# DIOT_signal_routing.net
KiCad netlist of a schematic drawn in Altium Designer
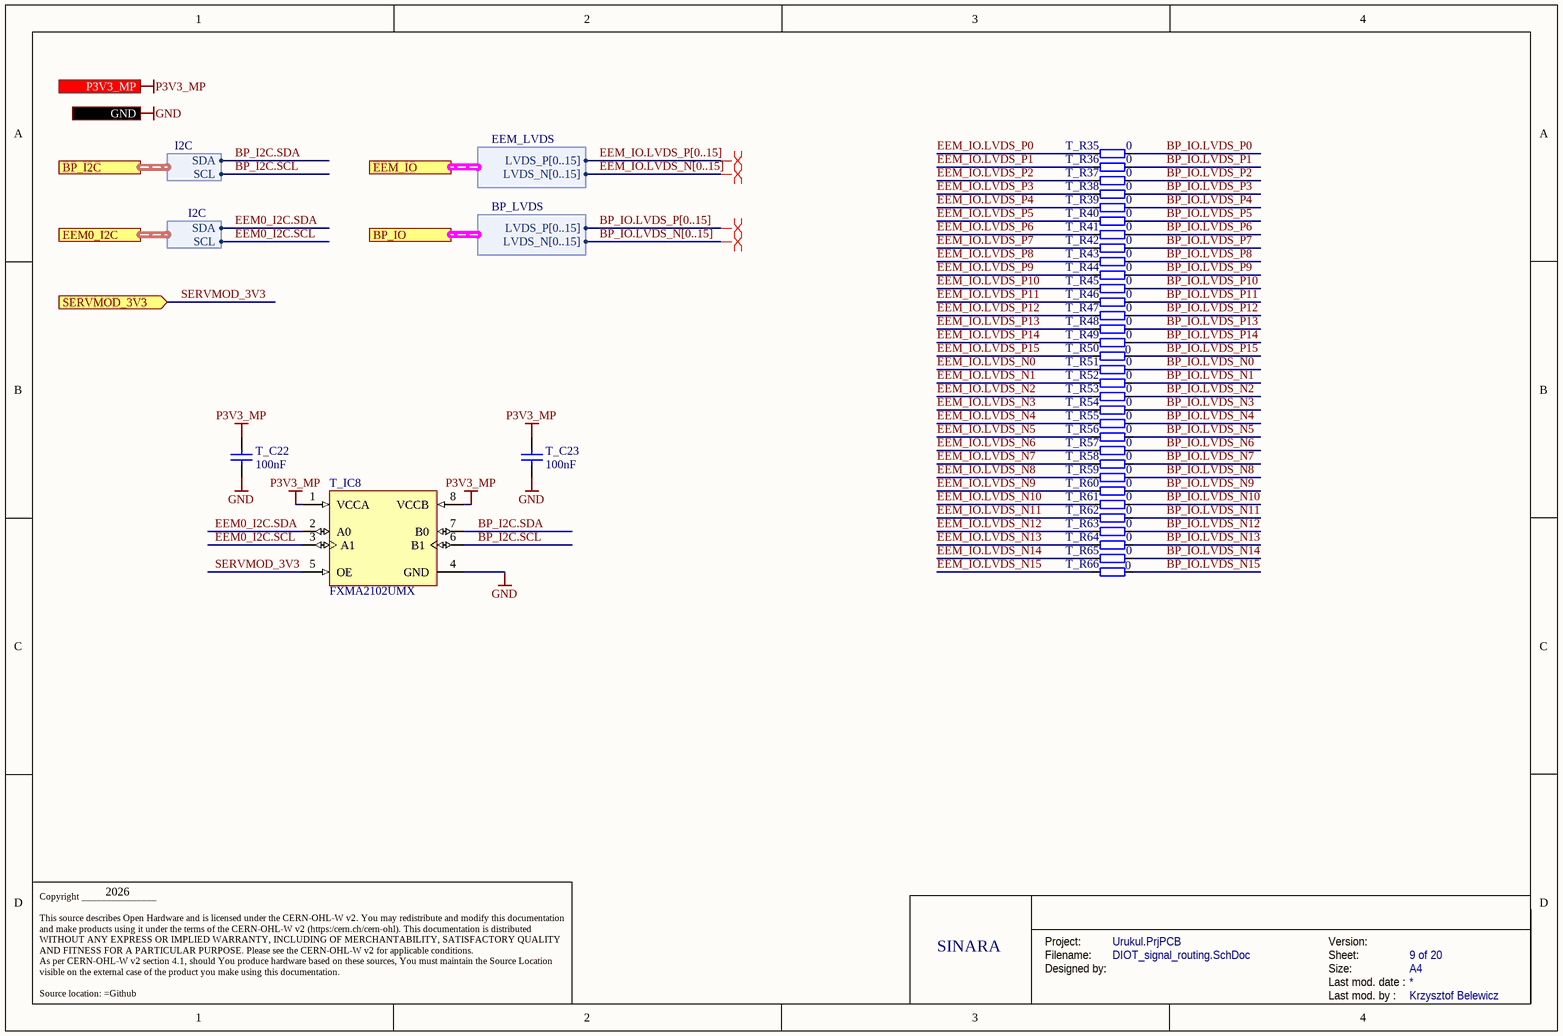
[diagram p0: DIOT_signal_routing.SchDoc]

(export (version "E")
  (design (tool "Eeschema 10.0.6"))
  (components
    (comp (ref "T_C22")
      (value "100nF")
      (footprint "CAPC1005X55N")
      (description "Non-polarised capacitor")
      (fields
        (field (name "PART NUMBER") "CC0402_100NF_16V_10%_X5R")
        (field (name "VOLTAGE") "16V")
        (field (name "AUTHOR") "CERN DEM JLC")
      )
      (libsource (lib "Capacitors") (part "Capacitor - non polarized"))
    )
    (comp (ref "T_C23")
      (value "100nF")
      (footprint "CAPC1005X55N")
      (description "Non-polarised capacitor")
      (fields
        (field (name "PART NUMBER") "CC0402_100NF_16V_10%_X5R")
        (field (name "VOLTAGE") "16V")
        (field (name "AUTHOR") "CERN DEM JLC")
      )
      (libsource (lib "Capacitors") (part "Capacitor - non polarized"))
    )
    (comp (ref "T_IC8")
      (value "FXMA2102UMX")
      (footprint "FXMA2102UMX")
      (description "Dual Supply 2-Bit Voltage Translator/Buffer/Repeater Isolator for I2C Applications")
      (fields (field (name "MANUFACTURER") "Onsemi"))
      (libsource (lib "TechnoSystem Workspace") (part "FXMA2102UMX"))
    )
    (comp (ref "T_R35")
      (value "0")
      (footprint "RESC1005X40N")
      (description "Resistor")
      (fields
        (field (name "PART NUMBER") "R0402_0R_JUMPER")
        (field (name "MANUFACTURER") "GENERIC")
        (field (name "AUTHOR") "CERN DEM JLC")
      )
      (libsource (lib "Resistors") (part "Resistor"))
    )
    (comp (ref "T_R36")
      (value "0")
      (footprint "RESC1005X40N")
      (description "Resistor")
      (fields
        (field (name "PART NUMBER") "R0402_0R_JUMPER")
        (field (name "MANUFACTURER") "GENERIC")
        (field (name "AUTHOR") "CERN DEM JLC")
      )
      (libsource (lib "Resistors") (part "Resistor"))
    )
    (comp (ref "T_R37")
      (value "0")
      (footprint "RESC1005X40N")
      (description "Resistor")
      (fields
        (field (name "PART NUMBER") "R0402_0R_JUMPER")
        (field (name "MANUFACTURER") "GENERIC")
        (field (name "AUTHOR") "CERN DEM JLC")
      )
      (libsource (lib "Resistors") (part "Resistor"))
    )
    (comp (ref "T_R38")
      (value "0")
      (footprint "RESC1005X40N")
      (description "Resistor")
      (fields
        (field (name "PART NUMBER") "R0402_0R_JUMPER")
        (field (name "MANUFACTURER") "GENERIC")
        (field (name "AUTHOR") "CERN DEM JLC")
      )
      (libsource (lib "Resistors") (part "Resistor"))
    )
    (comp (ref "T_R39")
      (value "0")
      (footprint "RESC1005X40N")
      (description "Resistor")
      (fields
        (field (name "PART NUMBER") "R0402_0R_JUMPER")
        (field (name "MANUFACTURER") "GENERIC")
        (field (name "AUTHOR") "CERN DEM JLC")
      )
      (libsource (lib "Resistors") (part "Resistor"))
    )
    (comp (ref "T_R40")
      (value "0")
      (footprint "RESC1005X40N")
      (description "Resistor")
      (fields
        (field (name "PART NUMBER") "R0402_0R_JUMPER")
        (field (name "MANUFACTURER") "GENERIC")
        (field (name "AUTHOR") "CERN DEM JLC")
      )
      (libsource (lib "Resistors") (part "Resistor"))
    )
    (comp (ref "T_R41")
      (value "0")
      (footprint "RESC1005X40N")
      (description "Resistor")
      (fields
        (field (name "PART NUMBER") "R0402_0R_JUMPER")
        (field (name "MANUFACTURER") "GENERIC")
        (field (name "AUTHOR") "CERN DEM JLC")
      )
      (libsource (lib "Resistors") (part "Resistor"))
    )
    (comp (ref "T_R42")
      (value "0")
      (footprint "RESC1005X40N")
      (description "Resistor")
      (fields
        (field (name "PART NUMBER") "R0402_0R_JUMPER")
        (field (name "MANUFACTURER") "GENERIC")
        (field (name "AUTHOR") "CERN DEM JLC")
      )
      (libsource (lib "Resistors") (part "Resistor"))
    )
    (comp (ref "T_R43")
      (value "0")
      (footprint "RESC1005X40N")
      (description "Resistor")
      (fields
        (field (name "PART NUMBER") "R0402_0R_JUMPER")
        (field (name "MANUFACTURER") "GENERIC")
        (field (name "AUTHOR") "CERN DEM JLC")
      )
      (libsource (lib "Resistors") (part "Resistor"))
    )
    (comp (ref "T_R44")
      (value "0")
      (footprint "RESC1005X40N")
      (description "Resistor")
      (fields
        (field (name "PART NUMBER") "R0402_0R_JUMPER")
        (field (name "MANUFACTURER") "GENERIC")
        (field (name "AUTHOR") "CERN DEM JLC")
      )
      (libsource (lib "Resistors") (part "Resistor"))
    )
    (comp (ref "T_R45")
      (value "0")
      (footprint "RESC1005X40N")
      (description "Resistor")
      (fields
        (field (name "PART NUMBER") "R0402_0R_JUMPER")
        (field (name "MANUFACTURER") "GENERIC")
        (field (name "AUTHOR") "CERN DEM JLC")
      )
      (libsource (lib "Resistors") (part "Resistor"))
    )
    (comp (ref "T_R46")
      (value "0")
      (footprint "RESC1005X40N")
      (description "Resistor")
      (fields
        (field (name "PART NUMBER") "R0402_0R_JUMPER")
        (field (name "MANUFACTURER") "GENERIC")
        (field (name "AUTHOR") "CERN DEM JLC")
      )
      (libsource (lib "Resistors") (part "Resistor"))
    )
    (comp (ref "T_R47")
      (value "0")
      (footprint "RESC1005X40N")
      (description "Resistor")
      (fields
        (field (name "PART NUMBER") "R0402_0R_JUMPER")
        (field (name "MANUFACTURER") "GENERIC")
        (field (name "AUTHOR") "CERN DEM JLC")
      )
      (libsource (lib "Resistors") (part "Resistor"))
    )
    (comp (ref "T_R48")
      (value "0")
      (footprint "RESC1005X40N")
      (description "Resistor")
      (fields
        (field (name "PART NUMBER") "R0402_0R_JUMPER")
        (field (name "MANUFACTURER") "GENERIC")
        (field (name "AUTHOR") "CERN DEM JLC")
      )
      (libsource (lib "Resistors") (part "Resistor"))
    )
    (comp (ref "T_R49")
      (value "0")
      (footprint "RESC1005X40N")
      (description "Resistor")
      (fields
        (field (name "PART NUMBER") "R0402_0R_JUMPER")
        (field (name "MANUFACTURER") "GENERIC")
        (field (name "AUTHOR") "CERN DEM JLC")
      )
      (libsource (lib "Resistors") (part "Resistor"))
    )
    (comp (ref "T_R50")
      (value "0")
      (footprint "RESC1005X40N")
      (description "Resistor")
      (fields
        (field (name "PART NUMBER") "R0402_0R_JUMPER")
        (field (name "MANUFACTURER") "GENERIC")
        (field (name "AUTHOR") "CERN DEM JLC")
      )
      (libsource (lib "Resistors") (part "Resistor"))
    )
    (comp (ref "T_R51")
      (value "0")
      (footprint "RESC1005X40N")
      (description "Resistor")
      (fields
        (field (name "PART NUMBER") "R0402_0R_JUMPER")
        (field (name "MANUFACTURER") "GENERIC")
        (field (name "AUTHOR") "CERN DEM JLC")
      )
      (libsource (lib "Resistors") (part "Resistor"))
    )
    (comp (ref "T_R52")
      (value "0")
      (footprint "RESC1005X40N")
      (description "Resistor")
      (fields
        (field (name "PART NUMBER") "R0402_0R_JUMPER")
        (field (name "MANUFACTURER") "GENERIC")
        (field (name "AUTHOR") "CERN DEM JLC")
      )
      (libsource (lib "Resistors") (part "Resistor"))
    )
    (comp (ref "T_R53")
      (value "0")
      (footprint "RESC1005X40N")
      (description "Resistor")
      (fields
        (field (name "PART NUMBER") "R0402_0R_JUMPER")
        (field (name "MANUFACTURER") "GENERIC")
        (field (name "AUTHOR") "CERN DEM JLC")
      )
      (libsource (lib "Resistors") (part "Resistor"))
    )
    (comp (ref "T_R54")
      (value "0")
      (footprint "RESC1005X40N")
      (description "Resistor")
      (fields
        (field (name "PART NUMBER") "R0402_0R_JUMPER")
        (field (name "MANUFACTURER") "GENERIC")
        (field (name "AUTHOR") "CERN DEM JLC")
      )
      (libsource (lib "Resistors") (part "Resistor"))
    )
    (comp (ref "T_R55")
      (value "0")
      (footprint "RESC1005X40N")
      (description "Resistor")
      (fields
        (field (name "PART NUMBER") "R0402_0R_JUMPER")
        (field (name "MANUFACTURER") "GENERIC")
        (field (name "AUTHOR") "CERN DEM JLC")
      )
      (libsource (lib "Resistors") (part "Resistor"))
    )
    (comp (ref "T_R56")
      (value "0")
      (footprint "RESC1005X40N")
      (description "Resistor")
      (fields
        (field (name "PART NUMBER") "R0402_0R_JUMPER")
        (field (name "MANUFACTURER") "GENERIC")
        (field (name "AUTHOR") "CERN DEM JLC")
      )
      (libsource (lib "Resistors") (part "Resistor"))
    )
    (comp (ref "T_R57")
      (value "0")
      (footprint "RESC1005X40N")
      (description "Resistor")
      (fields
        (field (name "PART NUMBER") "R0402_0R_JUMPER")
        (field (name "MANUFACTURER") "GENERIC")
        (field (name "AUTHOR") "CERN DEM JLC")
      )
      (libsource (lib "Resistors") (part "Resistor"))
    )
    (comp (ref "T_R58")
      (value "0")
      (footprint "RESC1005X40N")
      (description "Resistor")
      (fields
        (field (name "PART NUMBER") "R0402_0R_JUMPER")
        (field (name "MANUFACTURER") "GENERIC")
        (field (name "AUTHOR") "CERN DEM JLC")
      )
      (libsource (lib "Resistors") (part "Resistor"))
    )
    (comp (ref "T_R59")
      (value "0")
      (footprint "RESC1005X40N")
      (description "Resistor")
      (fields
        (field (name "PART NUMBER") "R0402_0R_JUMPER")
        (field (name "MANUFACTURER") "GENERIC")
        (field (name "AUTHOR") "CERN DEM JLC")
      )
      (libsource (lib "Resistors") (part "Resistor"))
    )
    (comp (ref "T_R60")
      (value "0")
      (footprint "RESC1005X40N")
      (description "Resistor")
      (fields
        (field (name "PART NUMBER") "R0402_0R_JUMPER")
        (field (name "MANUFACTURER") "GENERIC")
        (field (name "AUTHOR") "CERN DEM JLC")
      )
      (libsource (lib "Resistors") (part "Resistor"))
    )
    (comp (ref "T_R61")
      (value "0")
      (footprint "RESC1005X40N")
      (description "Resistor")
      (fields
        (field (name "PART NUMBER") "R0402_0R_JUMPER")
        (field (name "MANUFACTURER") "GENERIC")
        (field (name "AUTHOR") "CERN DEM JLC")
      )
      (libsource (lib "Resistors") (part "Resistor"))
    )
    (comp (ref "T_R62")
      (value "0")
      (footprint "RESC1005X40N")
      (description "Resistor")
      (fields
        (field (name "PART NUMBER") "R0402_0R_JUMPER")
        (field (name "MANUFACTURER") "GENERIC")
        (field (name "AUTHOR") "CERN DEM JLC")
      )
      (libsource (lib "Resistors") (part "Resistor"))
    )
    (comp (ref "T_R63")
      (value "0")
      (footprint "RESC1005X40N")
      (description "Resistor")
      (fields
        (field (name "PART NUMBER") "R0402_0R_JUMPER")
        (field (name "MANUFACTURER") "GENERIC")
        (field (name "AUTHOR") "CERN DEM JLC")
      )
      (libsource (lib "Resistors") (part "Resistor"))
    )
    (comp (ref "T_R64")
      (value "0")
      (footprint "RESC1005X40N")
      (description "Resistor")
      (fields
        (field (name "PART NUMBER") "R0402_0R_JUMPER")
        (field (name "MANUFACTURER") "GENERIC")
        (field (name "AUTHOR") "CERN DEM JLC")
      )
      (libsource (lib "Resistors") (part "Resistor"))
    )
    (comp (ref "T_R65")
      (value "0")
      (footprint "RESC1005X40N")
      (description "Resistor")
      (fields
        (field (name "PART NUMBER") "R0402_0R_JUMPER")
        (field (name "MANUFACTURER") "GENERIC")
        (field (name "AUTHOR") "CERN DEM JLC")
      )
      (libsource (lib "Resistors") (part "Resistor"))
    )
    (comp (ref "T_R66")
      (value "0")
      (footprint "RESC1005X40N")
      (description "Resistor")
      (fields
        (field (name "PART NUMBER") "R0402_0R_JUMPER")
        (field (name "MANUFACTURER") "GENERIC")
        (field (name "AUTHOR") "CERN DEM JLC")
      )
      (libsource (lib "Resistors") (part "Resistor"))
    )
  )
  (nets
    (net (code "4") (name "/BP_I2C.SCL") (class "Default")
      (node (ref "T_IC8") (pin "6") (pinfunction "B1_6") (pintype "bidirectional"))
    )
    (net (code "5") (name "/BP_I2C.SDA") (class "Default")
      (node (ref "T_IC8") (pin "7") (pinfunction "B0_7") (pintype "bidirectional"))
    )
    (net (code "6") (name "/BP_IO.LVDS_N0") (class "Default")
      (node (ref "T_R51") (pin "1") (pinfunction "1_1") (pintype "passive"))
    )
    (net (code "7") (name "/BP_IO.LVDS_N1") (class "Default")
      (node (ref "T_R52") (pin "1") (pinfunction "1_1") (pintype "passive"))
    )
    (net (code "8") (name "/BP_IO.LVDS_N2") (class "Default")
      (node (ref "T_R53") (pin "1") (pinfunction "1_1") (pintype "passive"))
    )
    (net (code "9") (name "/BP_IO.LVDS_N3") (class "Default")
      (node (ref "T_R54") (pin "1") (pinfunction "1_1") (pintype "passive"))
    )
    (net (code "10") (name "/BP_IO.LVDS_N4") (class "Default")
      (node (ref "T_R55") (pin "1") (pinfunction "1_1") (pintype "passive"))
    )
    (net (code "11") (name "/BP_IO.LVDS_N5") (class "Default")
      (node (ref "T_R56") (pin "1") (pinfunction "1_1") (pintype "passive"))
    )
    (net (code "12") (name "/BP_IO.LVDS_N6") (class "Default")
      (node (ref "T_R57") (pin "1") (pinfunction "1_1") (pintype "passive"))
    )
    (net (code "13") (name "/BP_IO.LVDS_N7") (class "Default")
      (node (ref "T_R58") (pin "1") (pinfunction "1_1") (pintype "passive"))
    )
    (net (code "14") (name "/BP_IO.LVDS_N8") (class "Default")
      (node (ref "T_R59") (pin "1") (pinfunction "1_1") (pintype "passive"))
    )
    (net (code "15") (name "/BP_IO.LVDS_N9") (class "Default")
      (node (ref "T_R60") (pin "1") (pinfunction "1_1") (pintype "passive"))
    )
    (net (code "16") (name "/BP_IO.LVDS_N10") (class "Default")
      (node (ref "T_R61") (pin "1") (pinfunction "1_1") (pintype "passive"))
    )
    (net (code "17") (name "/BP_IO.LVDS_N11") (class "Default")
      (node (ref "T_R62") (pin "1") (pinfunction "1_1") (pintype "passive"))
    )
    (net (code "18") (name "/BP_IO.LVDS_N12") (class "Default")
      (node (ref "T_R63") (pin "1") (pinfunction "1_1") (pintype "passive"))
    )
    (net (code "19") (name "/BP_IO.LVDS_N13") (class "Default")
      (node (ref "T_R64") (pin "1") (pinfunction "1_1") (pintype "passive"))
    )
    (net (code "20") (name "/BP_IO.LVDS_N14") (class "Default")
      (node (ref "T_R65") (pin "1") (pinfunction "1_1") (pintype "passive"))
    )
    (net (code "21") (name "/BP_IO.LVDS_N15") (class "Default")
      (node (ref "T_R66") (pin "2") (pinfunction "2_2") (pintype "passive"))
    )
    (net (code "22") (name "/BP_IO.LVDS_P0") (class "Default")
      (node (ref "T_R35") (pin "1") (pinfunction "1_1") (pintype "passive"))
    )
    (net (code "23") (name "/BP_IO.LVDS_P1") (class "Default")
      (node (ref "T_R36") (pin "1") (pinfunction "1_1") (pintype "passive"))
    )
    (net (code "24") (name "/BP_IO.LVDS_P2") (class "Default")
      (node (ref "T_R37") (pin "1") (pinfunction "1_1") (pintype "passive"))
    )
    (net (code "25") (name "/BP_IO.LVDS_P3") (class "Default")
      (node (ref "T_R38") (pin "1") (pinfunction "1_1") (pintype "passive"))
    )
    (net (code "26") (name "/BP_IO.LVDS_P4") (class "Default")
      (node (ref "T_R39") (pin "1") (pinfunction "1_1") (pintype "passive"))
    )
    (net (code "27") (name "/BP_IO.LVDS_P5") (class "Default")
      (node (ref "T_R40") (pin "1") (pinfunction "1_1") (pintype "passive"))
    )
    (net (code "28") (name "/BP_IO.LVDS_P6") (class "Default")
      (node (ref "T_R41") (pin "1") (pinfunction "1_1") (pintype "passive"))
    )
    (net (code "29") (name "/BP_IO.LVDS_P7") (class "Default")
      (node (ref "T_R42") (pin "1") (pinfunction "1_1") (pintype "passive"))
    )
    (net (code "30") (name "/BP_IO.LVDS_P8") (class "Default")
      (node (ref "T_R43") (pin "1") (pinfunction "1_1") (pintype "passive"))
    )
    (net (code "31") (name "/BP_IO.LVDS_P9") (class "Default")
      (node (ref "T_R44") (pin "1") (pinfunction "1_1") (pintype "passive"))
    )
    (net (code "32") (name "/BP_IO.LVDS_P10") (class "Default")
      (node (ref "T_R45") (pin "1") (pinfunction "1_1") (pintype "passive"))
    )
    (net (code "33") (name "/BP_IO.LVDS_P11") (class "Default")
      (node (ref "T_R46") (pin "1") (pinfunction "1_1") (pintype "passive"))
    )
    (net (code "34") (name "/BP_IO.LVDS_P12") (class "Default")
      (node (ref "T_R47") (pin "1") (pinfunction "1_1") (pintype "passive"))
    )
    (net (code "35") (name "/BP_IO.LVDS_P13") (class "Default")
      (node (ref "T_R48") (pin "1") (pinfunction "1_1") (pintype "passive"))
    )
    (net (code "36") (name "/BP_IO.LVDS_P14") (class "Default")
      (node (ref "T_R49") (pin "1") (pinfunction "1_1") (pintype "passive"))
    )
    (net (code "37") (name "/BP_IO.LVDS_P15") (class "Default")
      (node (ref "T_R50") (pin "2") (pinfunction "2_2") (pintype "passive"))
    )
    (net (code "40") (name "/EEM0_I2C.SCL") (class "Default")
      (node (ref "T_IC8") (pin "3") (pinfunction "A1_3") (pintype "bidirectional"))
    )
    (net (code "41") (name "/EEM0_I2C.SDA") (class "Default")
      (node (ref "T_IC8") (pin "2") (pinfunction "A0_2") (pintype "bidirectional"))
    )
    (net (code "42") (name "/EEM_IO.LVDS_N0") (class "Default")
      (node (ref "T_R51") (pin "2") (pinfunction "2_2") (pintype "passive"))
    )
    (net (code "43") (name "/EEM_IO.LVDS_N1") (class "Default")
      (node (ref "T_R52") (pin "2") (pinfunction "2_2") (pintype "passive"))
    )
    (net (code "44") (name "/EEM_IO.LVDS_N2") (class "Default")
      (node (ref "T_R53") (pin "2") (pinfunction "2_2") (pintype "passive"))
    )
    (net (code "45") (name "/EEM_IO.LVDS_N3") (class "Default")
      (node (ref "T_R54") (pin "2") (pinfunction "2_2") (pintype "passive"))
    )
    (net (code "46") (name "/EEM_IO.LVDS_N4") (class "Default")
      (node (ref "T_R55") (pin "2") (pinfunction "2_2") (pintype "passive"))
    )
    (net (code "47") (name "/EEM_IO.LVDS_N5") (class "Default")
      (node (ref "T_R56") (pin "2") (pinfunction "2_2") (pintype "passive"))
    )
    (net (code "48") (name "/EEM_IO.LVDS_N6") (class "Default")
      (node (ref "T_R57") (pin "2") (pinfunction "2_2") (pintype "passive"))
    )
    (net (code "49") (name "/EEM_IO.LVDS_N7") (class "Default")
      (node (ref "T_R58") (pin "2") (pinfunction "2_2") (pintype "passive"))
    )
    (net (code "50") (name "/EEM_IO.LVDS_N8") (class "Default")
      (node (ref "T_R59") (pin "2") (pinfunction "2_2") (pintype "passive"))
    )
    (net (code "51") (name "/EEM_IO.LVDS_N9") (class "Default")
      (node (ref "T_R60") (pin "2") (pinfunction "2_2") (pintype "passive"))
    )
    (net (code "52") (name "/EEM_IO.LVDS_N10") (class "Default")
      (node (ref "T_R61") (pin "2") (pinfunction "2_2") (pintype "passive"))
    )
    (net (code "53") (name "/EEM_IO.LVDS_N11") (class "Default")
      (node (ref "T_R62") (pin "2") (pinfunction "2_2") (pintype "passive"))
    )
    (net (code "54") (name "/EEM_IO.LVDS_N12") (class "Default")
      (node (ref "T_R63") (pin "2") (pinfunction "2_2") (pintype "passive"))
    )
    (net (code "55") (name "/EEM_IO.LVDS_N13") (class "Default")
      (node (ref "T_R64") (pin "2") (pinfunction "2_2") (pintype "passive"))
    )
    (net (code "56") (name "/EEM_IO.LVDS_N14") (class "Default")
      (node (ref "T_R65") (pin "2") (pinfunction "2_2") (pintype "passive"))
    )
    (net (code "57") (name "/EEM_IO.LVDS_N15") (class "Default")
      (node (ref "T_R66") (pin "1") (pinfunction "1_1") (pintype "passive"))
    )
    (net (code "59") (name "/EEM_IO.LVDS_P0") (class "Default")
      (node (ref "T_R35") (pin "2") (pinfunction "2_2") (pintype "passive"))
    )
    (net (code "60") (name "/EEM_IO.LVDS_P1") (class "Default")
      (node (ref "T_R36") (pin "2") (pinfunction "2_2") (pintype "passive"))
    )
    (net (code "61") (name "/EEM_IO.LVDS_P2") (class "Default")
      (node (ref "T_R37") (pin "2") (pinfunction "2_2") (pintype "passive"))
    )
    (net (code "62") (name "/EEM_IO.LVDS_P3") (class "Default")
      (node (ref "T_R38") (pin "2") (pinfunction "2_2") (pintype "passive"))
    )
    (net (code "63") (name "/EEM_IO.LVDS_P4") (class "Default")
      (node (ref "T_R39") (pin "2") (pinfunction "2_2") (pintype "passive"))
    )
    (net (code "64") (name "/EEM_IO.LVDS_P5") (class "Default")
      (node (ref "T_R40") (pin "2") (pinfunction "2_2") (pintype "passive"))
    )
    (net (code "65") (name "/EEM_IO.LVDS_P6") (class "Default")
      (node (ref "T_R41") (pin "2") (pinfunction "2_2") (pintype "passive"))
    )
    (net (code "66") (name "/EEM_IO.LVDS_P7") (class "Default")
      (node (ref "T_R42") (pin "2") (pinfunction "2_2") (pintype "passive"))
    )
    (net (code "67") (name "/EEM_IO.LVDS_P8") (class "Default")
      (node (ref "T_R43") (pin "2") (pinfunction "2_2") (pintype "passive"))
    )
    (net (code "68") (name "/EEM_IO.LVDS_P9") (class "Default")
      (node (ref "T_R44") (pin "2") (pinfunction "2_2") (pintype "passive"))
    )
    (net (code "69") (name "/EEM_IO.LVDS_P10") (class "Default")
      (node (ref "T_R45") (pin "2") (pinfunction "2_2") (pintype "passive"))
    )
    (net (code "70") (name "/EEM_IO.LVDS_P11") (class "Default")
      (node (ref "T_R46") (pin "2") (pinfunction "2_2") (pintype "passive"))
    )
    (net (code "71") (name "/EEM_IO.LVDS_P12") (class "Default")
      (node (ref "T_R47") (pin "2") (pinfunction "2_2") (pintype "passive"))
    )
    (net (code "72") (name "/EEM_IO.LVDS_P13") (class "Default")
      (node (ref "T_R48") (pin "2") (pinfunction "2_2") (pintype "passive"))
    )
    (net (code "73") (name "/EEM_IO.LVDS_P14") (class "Default")
      (node (ref "T_R49") (pin "2") (pinfunction "2_2") (pintype "passive"))
    )
    (net (code "74") (name "/EEM_IO.LVDS_P15") (class "Default")
      (node (ref "T_R50") (pin "1") (pinfunction "1_1") (pintype "passive"))
    )
    (net (code "76") (name "/SERVMOD_3V3") (class "Default")
      (node (ref "T_IC8") (pin "5") (pinfunction "OE_5") (pintype "input"))
    )
    (net (code "79") (name "GND") (class "Default")
      (node (ref "T_C22") (pin "1") (pinfunction "1_1") (pintype "passive"))
      (node (ref "T_C23") (pin "1") (pinfunction "1_1") (pintype "passive"))
      (node (ref "T_IC8") (pin "4") (pinfunction "GND_4") (pintype "power_in"))
    )
    (net (code "80") (name "P3V3_MP") (class "Default")
      (node (ref "T_C22") (pin "2") (pinfunction "2_2") (pintype "passive"))
      (node (ref "T_C23") (pin "2") (pinfunction "2_2") (pintype "passive"))
      (node (ref "T_IC8") (pin "1") (pinfunction "VCCA_1") (pintype "input"))
      (node (ref "T_IC8") (pin "8") (pinfunction "VCCB_8") (pintype "input"))
    )
  )
)
